# Elan_Chip_Interface.net
KiCad netlist of a schematic drawn in Altium Designer
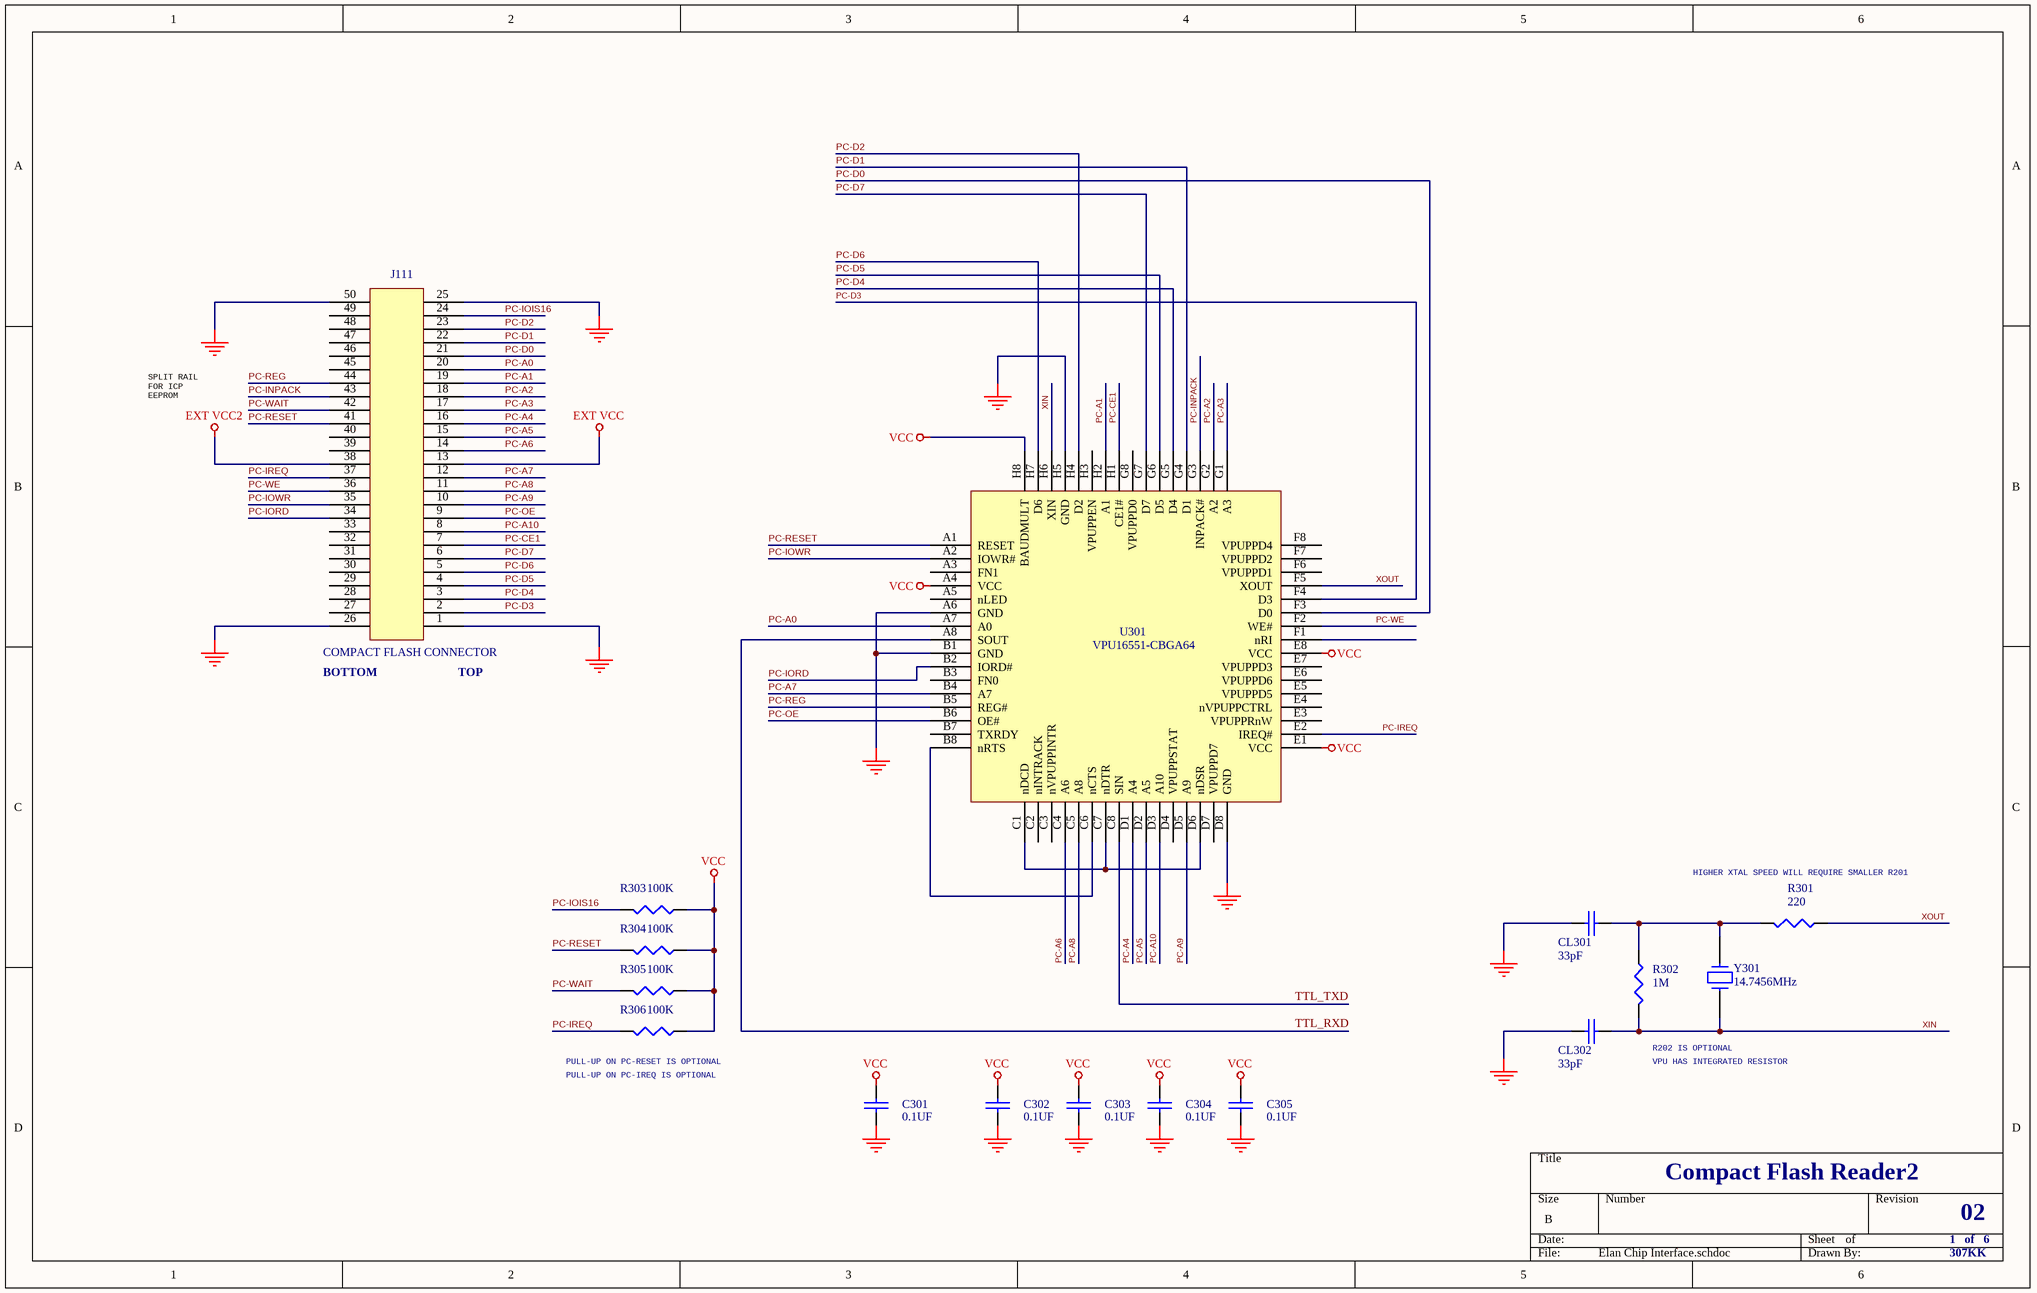
[diagram p0: Elan Chip Interface.schdoc]

(export (version "E")
  (design (tool "Eeschema 10.0.6"))
  (components
    (comp (ref "C301")
      (value "0.1UF")
      (footprint "0603")
      (description "Capacitor")
      (libsource (lib "*") (part "CAP"))
    )
    (comp (ref "C302")
      (value "0.1UF")
      (footprint "0603")
      (description "Capacitor")
      (libsource (lib "*") (part "CAP"))
    )
    (comp (ref "C303")
      (value "0.1UF")
      (footprint "0603")
      (description "Capacitor")
      (libsource (lib "*") (part "CAP"))
    )
    (comp (ref "C304")
      (value "0.1UF")
      (footprint "0603")
      (description "Capacitor")
      (libsource (lib "*") (part "CAP"))
    )
    (comp (ref "C305")
      (value "0.1UF")
      (footprint "0603")
      (description "Capacitor")
      (libsource (lib "*") (part "CAP"))
    )
    (comp (ref "CL301")
      (value "33pF")
      (footprint "0603")
      (description "Capacitor")
      (libsource (lib "*") (part "CAP"))
    )
    (comp (ref "CL302")
      (value "33pF")
      (footprint "0603")
      (description "Capacitor")
      (libsource (lib "*") (part "CAP"))
    )
    (comp (ref "J111") (value "COMPACT FLASH CONNECTOR") (libsource (lib "Common") (part "CON50")))
    (comp (ref "R301") (value "220") (footprint "0603") (libsource (lib "*") (part "R")))
    (comp (ref "R302") (value "1M") (footprint "0603") (libsource (lib "*") (part "R")))
    (comp (ref "R303") (value "100K") (footprint "0603") (libsource (lib "*") (part "R")))
    (comp (ref "R304") (value "100K") (footprint "0603") (libsource (lib "*") (part "R")))
    (comp (ref "R305") (value "100K") (footprint "0603") (libsource (lib "*") (part "R")))
    (comp (ref "R306") (value "100K") (footprint "0603") (libsource (lib "*") (part "R")))
    (comp (ref "U301")
      (value "VPU16551-CBGA64")
      (footprint "BGA68")
      (libsource (lib "*") (part "VPU16551-CBGA64"))
    )
    (comp (ref "Y301")
      (value "14.7456MHz")
      (footprint "SMT CRYSTAL")
      (description "Crystal")
      (libsource (lib "*") (part "CRYSTAL"))
    )
  )
  (nets
    (net (code "1") (name "/PC-A0") (class "Default")
      (node (ref "J111") (pin "20") (pintype "passive"))
      (node (ref "U301") (pin "A7") (pinfunction "A0_A7") (pintype "passive"))
    )
    (net (code "2") (name "/PC-A1") (class "Default")
      (node (ref "J111") (pin "19") (pintype "passive"))
      (node (ref "U301") (pin "H2") (pinfunction "A1_H2") (pintype "passive"))
    )
    (net (code "3") (name "/PC-A2") (class "Default")
      (node (ref "J111") (pin "18") (pintype "passive"))
      (node (ref "U301") (pin "G2") (pinfunction "A2_G2") (pintype "passive"))
    )
    (net (code "4") (name "/PC-A3") (class "Default")
      (node (ref "J111") (pin "17") (pintype "passive"))
      (node (ref "U301") (pin "G1") (pinfunction "A3_G1") (pintype "passive"))
    )
    (net (code "5") (name "/PC-A4") (class "Default")
      (node (ref "J111") (pin "16") (pintype "passive"))
      (node (ref "U301") (pin "D1") (pinfunction "A4_D1") (pintype "passive"))
    )
    (net (code "6") (name "/PC-A5") (class "Default")
      (node (ref "J111") (pin "15") (pintype "passive"))
      (node (ref "U301") (pin "D2") (pinfunction "A5_D2") (pintype "passive"))
    )
    (net (code "7") (name "/PC-A6") (class "Default")
      (node (ref "J111") (pin "14") (pintype "passive"))
      (node (ref "U301") (pin "C4") (pinfunction "A6_C4") (pintype "passive"))
    )
    (net (code "8") (name "/PC-A7") (class "Default")
      (node (ref "J111") (pin "12") (pintype "passive"))
      (node (ref "U301") (pin "B4") (pinfunction "A7_B4") (pintype "passive"))
    )
    (net (code "9") (name "/PC-A8") (class "Default")
      (node (ref "J111") (pin "11") (pintype "passive"))
      (node (ref "U301") (pin "C5") (pinfunction "A8_C5") (pintype "passive"))
    )
    (net (code "10") (name "/PC-A9") (class "Default")
      (node (ref "J111") (pin "10") (pintype "passive"))
      (node (ref "U301") (pin "D5") (pinfunction "A9_D5") (pintype "passive"))
    )
    (net (code "11") (name "/PC-A10") (class "Default")
      (node (ref "J111") (pin "8") (pintype "passive"))
      (node (ref "U301") (pin "D3") (pinfunction "A10_D3") (pintype "passive"))
    )
    (net (code "12") (name "/PC-CE1") (class "Default")
      (node (ref "J111") (pin "7") (pintype "passive"))
      (node (ref "U301") (pin "H1") (pinfunction "CE1#_H1") (pintype "passive"))
    )
    (net (code "13") (name "/PC-D0") (class "Default")
      (node (ref "J111") (pin "21") (pintype "passive"))
      (node (ref "U301") (pin "F3") (pinfunction "D0_F3") (pintype "passive"))
    )
    (net (code "14") (name "/PC-D1") (class "Default")
      (node (ref "J111") (pin "22") (pintype "passive"))
      (node (ref "U301") (pin "G4") (pinfunction "D1_G4") (pintype "passive"))
    )
    (net (code "15") (name "/PC-D2") (class "Default")
      (node (ref "J111") (pin "23") (pintype "passive"))
      (node (ref "U301") (pin "H4") (pinfunction "D2_H4") (pintype "passive"))
    )
    (net (code "16") (name "/PC-D3") (class "Default")
      (node (ref "J111") (pin "2") (pintype "passive"))
      (node (ref "U301") (pin "F4") (pinfunction "D3_F4") (pintype "passive"))
    )
    (net (code "17") (name "/PC-D4") (class "Default")
      (node (ref "J111") (pin "3") (pintype "passive"))
      (node (ref "U301") (pin "G5") (pinfunction "D4_G5") (pintype "passive"))
    )
    (net (code "18") (name "/PC-D5") (class "Default")
      (node (ref "J111") (pin "4") (pintype "passive"))
      (node (ref "U301") (pin "G6") (pinfunction "D5_G6") (pintype "passive"))
    )
    (net (code "19") (name "/PC-D6") (class "Default")
      (node (ref "J111") (pin "5") (pintype "passive"))
      (node (ref "U301") (pin "H7") (pinfunction "D6_H7") (pintype "passive"))
    )
    (net (code "20") (name "/PC-D7") (class "Default")
      (node (ref "J111") (pin "6") (pintype "passive"))
      (node (ref "U301") (pin "G7") (pinfunction "D7_G7") (pintype "passive"))
    )
    (net (code "21") (name "/PC-INPACK") (class "Default")
      (node (ref "J111") (pin "43") (pintype "passive"))
      (node (ref "U301") (pin "G3") (pinfunction "INPACK#_G3") (pintype "passive"))
    )
    (net (code "22") (name "/PC-IOIS16") (class "Default")
      (node (ref "J111") (pin "24") (pintype "passive"))
      (node (ref "R303") (pin "2") (pinfunction "2_2") (pintype "passive"))
    )
    (net (code "23") (name "/PC-IORD") (class "Default")
      (node (ref "J111") (pin "34") (pintype "passive"))
      (node (ref "U301") (pin "B2") (pinfunction "IORD#_B2") (pintype "passive"))
    )
    (net (code "24") (name "/PC-IOWR") (class "Default")
      (node (ref "J111") (pin "35") (pintype "passive"))
      (node (ref "U301") (pin "A2") (pinfunction "IOWR#_A2") (pintype "passive"))
    )
    (net (code "25") (name "/PC-IREQ") (class "Default")
      (node (ref "J111") (pin "37") (pintype "passive"))
      (node (ref "R306") (pin "2") (pinfunction "2_2") (pintype "passive"))
      (node (ref "U301") (pin "E2") (pinfunction "IREQ#_E2") (pintype "passive"))
    )
    (net (code "26") (name "/PC-OE") (class "Default")
      (node (ref "J111") (pin "9") (pintype "passive"))
      (node (ref "U301") (pin "B6") (pinfunction "OE#_B6") (pintype "passive"))
    )
    (net (code "27") (name "/PC-REG") (class "Default")
      (node (ref "J111") (pin "44") (pintype "passive"))
      (node (ref "U301") (pin "B5") (pinfunction "REG#_B5") (pintype "passive"))
    )
    (net (code "28") (name "/PC-RESET") (class "Default")
      (node (ref "J111") (pin "41") (pintype "passive"))
      (node (ref "R304") (pin "2") (pinfunction "2_2") (pintype "passive"))
      (node (ref "U301") (pin "A1") (pinfunction "RESET_A1") (pintype "passive"))
    )
    (net (code "29") (name "/PC-WAIT") (class "Default")
      (node (ref "J111") (pin "42") (pintype "passive"))
      (node (ref "R305") (pin "2") (pinfunction "2_2") (pintype "passive"))
    )
    (net (code "30") (name "/PC-WE") (class "Default")
      (node (ref "J111") (pin "36") (pintype "passive"))
      (node (ref "U301") (pin "F2") (pinfunction "WE#_F2") (pintype "passive"))
    )
    (net (code "31") (name "/TTL_RXD") (class "Default")
      (node (ref "U301") (pin "A8") (pinfunction "SOUT_A8") (pintype "passive"))
    )
    (net (code "32") (name "/TTL_TXD") (class "Default")
      (node (ref "U301") (pin "C8") (pinfunction "SIN_C8") (pintype "passive"))
    )
    (net (code "33") (name "/XIN") (class "Default")
      (node (ref "CL302") (pin "1") (pinfunction "1_1") (pintype "passive"))
      (node (ref "R302") (pin "2") (pinfunction "2_2") (pintype "passive"))
      (node (ref "U301") (pin "H6") (pinfunction "XIN_H6") (pintype "passive"))
      (node (ref "Y301") (pin "1") (pinfunction "1_1") (pintype "passive"))
    )
    (net (code "34") (name "/XOUT") (class "Default")
      (node (ref "R301") (pin "1") (pinfunction "1_1") (pintype "passive"))
      (node (ref "U301") (pin "F5") (pinfunction "XOUT_F5") (pintype "passive"))
    )
    (net (code "35") (name "EXT VCC") (class "Default") (node (ref "J111") (pin "13") (pintype "passive")))
    (net (code "36") (name "EXT VCC2") (class "Default") (node (ref "J111") (pin "38") (pintype "passive")))
    (net (code "37") (name "GND_COM") (class "Default")
      (node (ref "C301") (pin "2") (pinfunction "2_2") (pintype "passive"))
      (node (ref "C302") (pin "2") (pinfunction "2_2") (pintype "passive"))
      (node (ref "C303") (pin "2") (pinfunction "2_2") (pintype "passive"))
      (node (ref "C304") (pin "2") (pinfunction "2_2") (pintype "passive"))
      (node (ref "C305") (pin "2") (pinfunction "2_2") (pintype "passive"))
      (node (ref "CL301") (pin "2") (pinfunction "2_2") (pintype "passive"))
      (node (ref "CL302") (pin "2") (pinfunction "2_2") (pintype "passive"))
      (node (ref "J111") (pin "1") (pintype "passive"))
      (node (ref "J111") (pin "25") (pintype "passive"))
      (node (ref "J111") (pin "26") (pintype "passive"))
      (node (ref "J111") (pin "50") (pintype "passive"))
      (node (ref "U301") (pin "A6") (pinfunction "GND_A6") (pintype "power_in"))
      (node (ref "U301") (pin "B1") (pinfunction "GND_B1") (pintype "power_in"))
      (node (ref "U301") (pin "D8") (pinfunction "GND_D8") (pintype "power_in"))
      (node (ref "U301") (pin "H5") (pinfunction "GND_H5") (pintype "power_in"))
    )
    (net (code "38") (name "Net-(CL301-Pad1)") (class "Default")
      (node (ref "CL301") (pin "1") (pinfunction "1_1") (pintype "passive"))
      (node (ref "R301") (pin "2") (pinfunction "2_2") (pintype "passive"))
      (node (ref "R302") (pin "1") (pinfunction "1_1") (pintype "passive"))
      (node (ref "Y301") (pin "2") (pinfunction "2_2") (pintype "passive"))
    )
    (net (code "39") (name "Net-(U301-nCTS)") (class "Default")
      (node (ref "U301") (pin "B8") (pinfunction "nRTS_B8") (pintype "passive"))
      (node (ref "U301") (pin "C6") (pinfunction "nCTS_C6") (pintype "passive"))
    )
    (net (code "40") (name "Net-(U301-nDCD)") (class "Default")
      (node (ref "U301") (pin "C1") (pinfunction "nDCD_C1") (pintype "passive"))
      (node (ref "U301") (pin "C7") (pinfunction "nDTR_C7") (pintype "passive"))
      (node (ref "U301") (pin "D6") (pinfunction "nDSR_D6") (pintype "passive"))
    )
    (net (code "41") (name "VCC") (class "Default")
      (node (ref "C301") (pin "1") (pinfunction "1_1") (pintype "passive"))
      (node (ref "C302") (pin "1") (pinfunction "1_1") (pintype "passive"))
      (node (ref "C303") (pin "1") (pinfunction "1_1") (pintype "passive"))
      (node (ref "C304") (pin "1") (pinfunction "1_1") (pintype "passive"))
      (node (ref "C305") (pin "1") (pinfunction "1_1") (pintype "passive"))
      (node (ref "R303") (pin "1") (pinfunction "1_1") (pintype "passive"))
      (node (ref "R304") (pin "1") (pinfunction "1_1") (pintype "passive"))
      (node (ref "R305") (pin "1") (pinfunction "1_1") (pintype "passive"))
      (node (ref "R306") (pin "1") (pinfunction "1_1") (pintype "passive"))
      (node (ref "U301") (pin "A4") (pinfunction "VCC_A4") (pintype "power_in"))
      (node (ref "U301") (pin "E1") (pinfunction "VCC_E1") (pintype "power_in"))
      (node (ref "U301") (pin "E8") (pinfunction "VCC_E8") (pintype "power_in"))
      (node (ref "U301") (pin "H8") (pinfunction "BAUDMULT_H8") (pintype "passive"))
    )
    (net (code "42") (name "unconnected-(J111-Pad27)") (class "Default")
      (node (ref "J111") (pin "27") (pintype "passive"))
    )
    (net (code "43") (name "unconnected-(J111-Pad28)") (class "Default")
      (node (ref "J111") (pin "28") (pintype "passive"))
    )
    (net (code "44") (name "unconnected-(J111-Pad29)") (class "Default")
      (node (ref "J111") (pin "29") (pintype "passive"))
    )
    (net (code "45") (name "unconnected-(J111-Pad30)") (class "Default")
      (node (ref "J111") (pin "30") (pintype "passive"))
    )
    (net (code "46") (name "unconnected-(J111-Pad31)") (class "Default")
      (node (ref "J111") (pin "31") (pintype "passive"))
    )
    (net (code "47") (name "unconnected-(J111-Pad32)") (class "Default")
      (node (ref "J111") (pin "32") (pintype "passive"))
    )
    (net (code "48") (name "unconnected-(J111-Pad33)") (class "Default")
      (node (ref "J111") (pin "33") (pintype "passive"))
    )
    (net (code "49") (name "unconnected-(J111-Pad39)") (class "Default")
      (node (ref "J111") (pin "39") (pintype "passive"))
    )
    (net (code "50") (name "unconnected-(J111-Pad40)") (class "Default")
      (node (ref "J111") (pin "40") (pintype "passive"))
    )
    (net (code "51") (name "unconnected-(J111-Pad45)") (class "Default")
      (node (ref "J111") (pin "45") (pintype "passive"))
    )
    (net (code "52") (name "unconnected-(J111-Pad46)") (class "Default")
      (node (ref "J111") (pin "46") (pintype "passive"))
    )
    (net (code "53") (name "unconnected-(J111-Pad47)") (class "Default")
      (node (ref "J111") (pin "47") (pintype "passive"))
    )
    (net (code "54") (name "unconnected-(J111-Pad48)") (class "Default")
      (node (ref "J111") (pin "48") (pintype "passive"))
    )
    (net (code "55") (name "unconnected-(J111-Pad49)") (class "Default")
      (node (ref "J111") (pin "49") (pintype "passive"))
    )
    (net (code "56") (name "unconnected-(U301-FN0-PadB3)") (class "Default")
      (node (ref "U301") (pin "B3") (pinfunction "FN0_B3") (pintype "passive"))
    )
    (net (code "57") (name "unconnected-(U301-FN1-PadA3)") (class "Default")
      (node (ref "U301") (pin "A3") (pinfunction "FN1_A3") (pintype "passive"))
    )
    (net (code "58") (name "unconnected-(U301-TXRDY-PadB7)") (class "Default")
      (node (ref "U301") (pin "B7") (pinfunction "TXRDY_B7") (pintype "passive"))
    )
    (net (code "59") (name "unconnected-(U301-VPUPPD0-PadG8)") (class "Default")
      (node (ref "U301") (pin "G8") (pinfunction "VPUPPD0_G8") (pintype "passive"))
    )
    (net (code "60") (name "unconnected-(U301-VPUPPD1-PadF6)") (class "Default")
      (node (ref "U301") (pin "F6") (pinfunction "VPUPPD1_F6") (pintype "passive"))
    )
    (net (code "61") (name "unconnected-(U301-VPUPPD2-PadF7)") (class "Default")
      (node (ref "U301") (pin "F7") (pinfunction "VPUPPD2_F7") (pintype "passive"))
    )
    (net (code "62") (name "unconnected-(U301-VPUPPD3-PadE7)") (class "Default")
      (node (ref "U301") (pin "E7") (pinfunction "VPUPPD3_E7") (pintype "passive"))
    )
    (net (code "63") (name "unconnected-(U301-VPUPPD4-PadF8)") (class "Default")
      (node (ref "U301") (pin "F8") (pinfunction "VPUPPD4_F8") (pintype "passive"))
    )
    (net (code "64") (name "unconnected-(U301-VPUPPD5-PadE5)") (class "Default")
      (node (ref "U301") (pin "E5") (pinfunction "VPUPPD5_E5") (pintype "passive"))
    )
    (net (code "65") (name "unconnected-(U301-VPUPPD6-PadE6)") (class "Default")
      (node (ref "U301") (pin "E6") (pinfunction "VPUPPD6_E6") (pintype "passive"))
    )
    (net (code "66") (name "unconnected-(U301-VPUPPD7-PadD7)") (class "Default")
      (node (ref "U301") (pin "D7") (pinfunction "VPUPPD7_D7") (pintype "passive"))
    )
    (net (code "67") (name "unconnected-(U301-VPUPPEN-PadH3)") (class "Default")
      (node (ref "U301") (pin "H3") (pinfunction "VPUPPEN_H3") (pintype "passive"))
    )
    (net (code "68") (name "unconnected-(U301-VPUPPRnW-PadE3)") (class "Default")
      (node (ref "U301") (pin "E3") (pinfunction "VPUPPRnW_E3") (pintype "passive"))
    )
    (net (code "69") (name "unconnected-(U301-VPUPPSTAT-PadD4)") (class "Default")
      (node (ref "U301") (pin "D4") (pinfunction "VPUPPSTAT_D4") (pintype "passive"))
    )
    (net (code "70") (name "unconnected-(U301-nINTRACK-PadC2)") (class "Default")
      (node (ref "U301") (pin "C2") (pinfunction "nINTRACK_C2") (pintype "passive"))
    )
    (net (code "71") (name "unconnected-(U301-nLED-PadA5)") (class "Default")
      (node (ref "U301") (pin "A5") (pinfunction "nLED_A5") (pintype "passive"))
    )
    (net (code "72") (name "unconnected-(U301-nRI-PadF1)") (class "Default")
      (node (ref "U301") (pin "F1") (pinfunction "nRI_F1") (pintype "passive"))
    )
    (net (code "73") (name "unconnected-(U301-nVPUPPCTRL-PadE4)") (class "Default")
      (node (ref "U301") (pin "E4") (pinfunction "nVPUPPCTRL_E4") (pintype "passive"))
    )
    (net (code "74") (name "unconnected-(U301-nVPUPPINTR-PadC3)") (class "Default")
      (node (ref "U301") (pin "C3") (pinfunction "nVPUPPINTR_C3") (pintype "passive"))
    )
  )
)
